# WL-POWER.net
KiCad netlist of a schematic drawn in Altium Designer
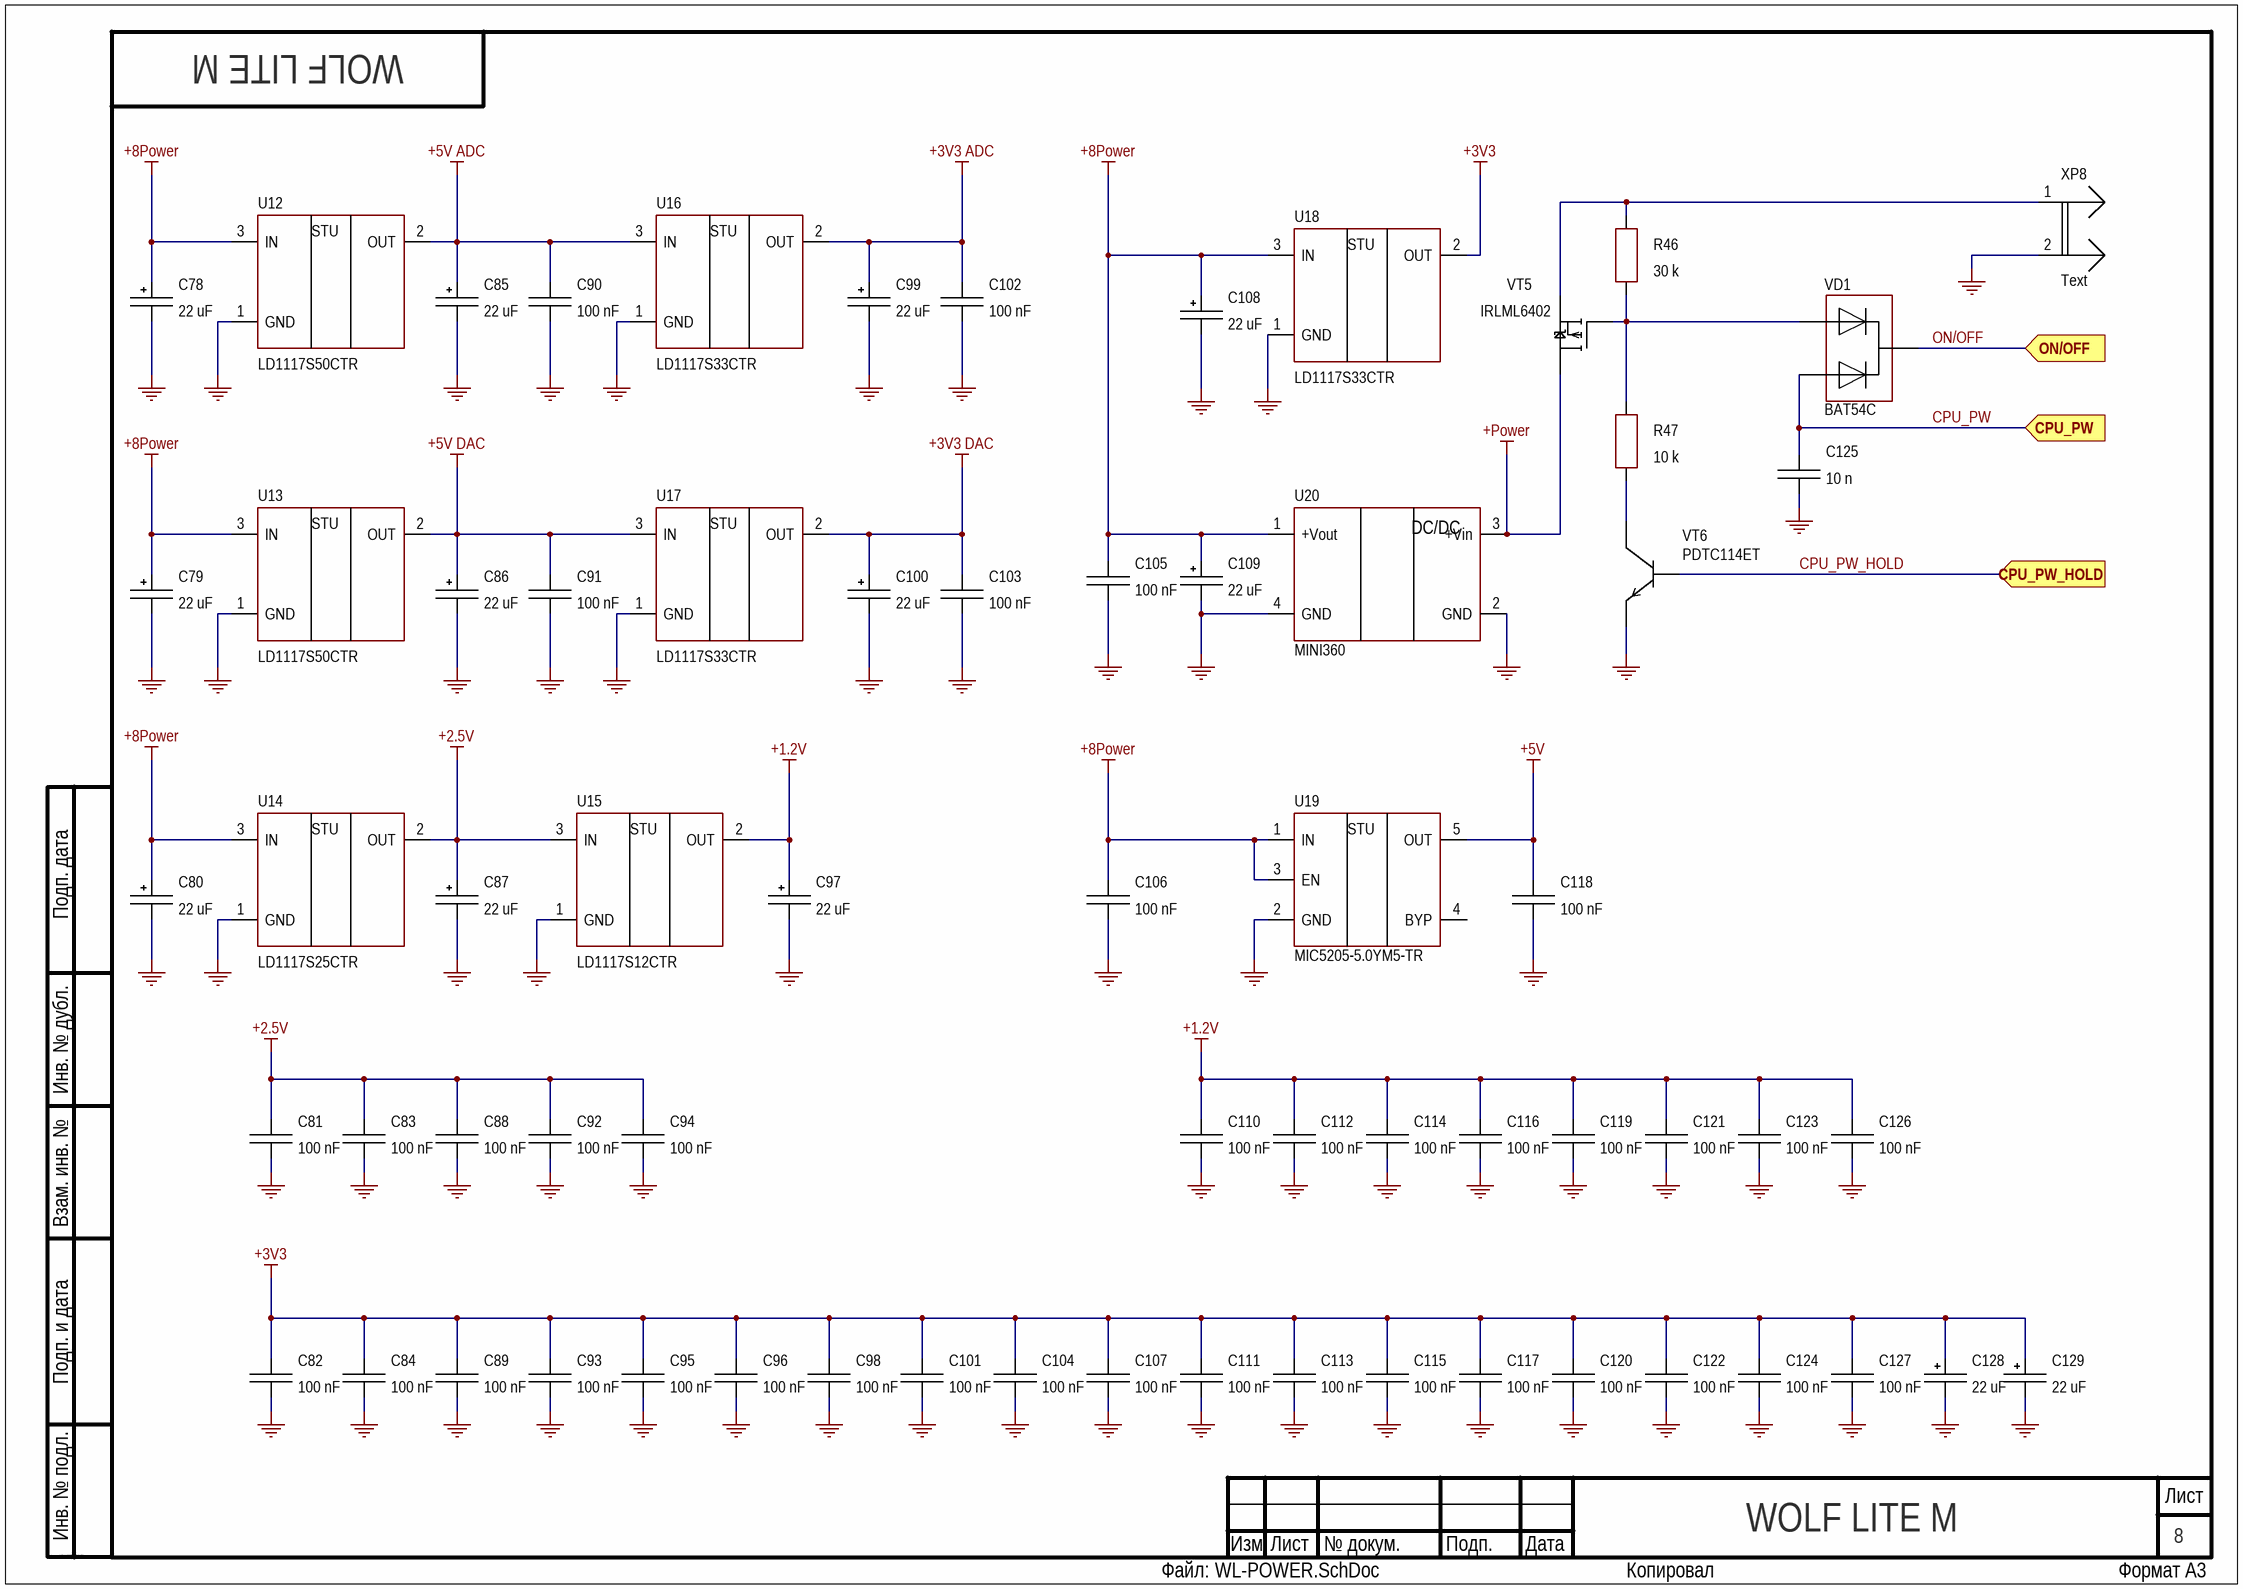
[diagram p0: WL-POWER.SchDoc]

(export (version "E")
  (design (tool "Eeschema 10.0.6"))
  (components
    (comp (ref "C78")
      (value "22 uF")
      (footprint "CAP-CASE B")
      (fields
        (field (name "MANUFACTURER") "Panasonic Electronic Components")
        (field (name "PART NUMBER") "EEE-1CA220WAR")
        (field (name "TOLERANCE") "±20%")
      )
      (libsource (lib "GOST") (part "Capacitor Polar"))
    )
    (comp (ref "C79")
      (value "22 uF")
      (footprint "CAP-CASE B")
      (fields
        (field (name "MANUFACTURER") "Panasonic Electronic Components")
        (field (name "PART NUMBER") "EEE-1CA220WAR")
        (field (name "TOLERANCE") "±20%")
      )
      (libsource (lib "GOST") (part "Capacitor Polar"))
    )
    (comp (ref "C80")
      (value "22 uF")
      (footprint "CAP-CASE B")
      (fields
        (field (name "MANUFACTURER") "Panasonic Electronic Components")
        (field (name "PART NUMBER") "EEE-1CA220WAR")
        (field (name "TOLERANCE") "±20%")
      )
      (libsource (lib "GOST") (part "Capacitor Polar"))
    )
    (comp (ref "C81")
      (value "100 nF")
      (footprint "C-0805-0.95")
      (fields
        (field (name "MANUFACTURER") "Yageo")
        (field (name "PART NUMBER") "CC0805KRX7R9BB104")
        (field (name "TOLERANCE") "±10%")
      )
      (libsource (lib "GOST") (part "Capacitor"))
    )
    (comp (ref "C82")
      (value "100 nF")
      (footprint "C-0805-0.95")
      (fields
        (field (name "MANUFACTURER") "Yageo")
        (field (name "PART NUMBER") "CC0805KRX7R9BB104")
        (field (name "TOLERANCE") "±10%")
      )
      (libsource (lib "GOST") (part "Capacitor"))
    )
    (comp (ref "C83")
      (value "100 nF")
      (footprint "C-0805-0.95")
      (fields
        (field (name "MANUFACTURER") "Yageo")
        (field (name "PART NUMBER") "CC0805KRX7R9BB104")
        (field (name "TOLERANCE") "±10%")
      )
      (libsource (lib "GOST") (part "Capacitor"))
    )
    (comp (ref "C84")
      (value "100 nF")
      (footprint "C-0805-0.95")
      (fields
        (field (name "MANUFACTURER") "Yageo")
        (field (name "PART NUMBER") "CC0805KRX7R9BB104")
        (field (name "TOLERANCE") "±10%")
      )
      (libsource (lib "GOST") (part "Capacitor"))
    )
    (comp (ref "C85")
      (value "22 uF")
      (footprint "CAP-CASE B")
      (fields
        (field (name "MANUFACTURER") "Panasonic Electronic Components")
        (field (name "PART NUMBER") "EEE-1CA220WAR")
        (field (name "TOLERANCE") "±20%")
      )
      (libsource (lib "GOST") (part "Capacitor Polar"))
    )
    (comp (ref "C86")
      (value "22 uF")
      (footprint "CAP-CASE B")
      (fields
        (field (name "MANUFACTURER") "Panasonic Electronic Components")
        (field (name "PART NUMBER") "EEE-1CA220WAR")
        (field (name "TOLERANCE") "±20%")
      )
      (libsource (lib "GOST") (part "Capacitor Polar"))
    )
    (comp (ref "C87")
      (value "22 uF")
      (footprint "CAP-CASE B")
      (fields
        (field (name "MANUFACTURER") "Panasonic Electronic Components")
        (field (name "PART NUMBER") "EEE-1CA220WAR")
        (field (name "TOLERANCE") "±20%")
      )
      (libsource (lib "GOST") (part "Capacitor Polar"))
    )
    (comp (ref "C88")
      (value "100 nF")
      (footprint "C-0805-0.95")
      (fields
        (field (name "MANUFACTURER") "Yageo")
        (field (name "PART NUMBER") "CC0805KRX7R9BB104")
        (field (name "TOLERANCE") "±10%")
      )
      (libsource (lib "GOST") (part "Capacitor"))
    )
    (comp (ref "C89")
      (value "100 nF")
      (footprint "C-0805-0.95")
      (fields
        (field (name "MANUFACTURER") "Yageo")
        (field (name "PART NUMBER") "CC0805KRX7R9BB104")
        (field (name "TOLERANCE") "±10%")
      )
      (libsource (lib "GOST") (part "Capacitor"))
    )
    (comp (ref "C90")
      (value "100 nF")
      (footprint "C-0805-0.95")
      (fields
        (field (name "MANUFACTURER") "Yageo")
        (field (name "PART NUMBER") "CC0805KRX7R9BB104")
        (field (name "TOLERANCE") "±10%")
      )
      (libsource (lib "GOST") (part "Capacitor"))
    )
    (comp (ref "C91")
      (value "100 nF")
      (footprint "C-0805-0.95")
      (fields
        (field (name "MANUFACTURER") "Yageo")
        (field (name "PART NUMBER") "CC0805KRX7R9BB104")
        (field (name "TOLERANCE") "±10%")
      )
      (libsource (lib "GOST") (part "Capacitor"))
    )
    (comp (ref "C92")
      (value "100 nF")
      (footprint "C-0805-0.95")
      (fields
        (field (name "MANUFACTURER") "Yageo")
        (field (name "PART NUMBER") "CC0805KRX7R9BB104")
        (field (name "TOLERANCE") "±10%")
      )
      (libsource (lib "GOST") (part "Capacitor"))
    )
    (comp (ref "C93")
      (value "100 nF")
      (footprint "C-0805-0.95")
      (fields
        (field (name "MANUFACTURER") "Yageo")
        (field (name "PART NUMBER") "CC0805KRX7R9BB104")
        (field (name "TOLERANCE") "±10%")
      )
      (libsource (lib "GOST") (part "Capacitor"))
    )
    (comp (ref "C94")
      (value "100 nF")
      (footprint "C-0805-0.95")
      (fields
        (field (name "MANUFACTURER") "Yageo")
        (field (name "PART NUMBER") "CC0805KRX7R9BB104")
        (field (name "TOLERANCE") "±10%")
      )
      (libsource (lib "GOST") (part "Capacitor"))
    )
    (comp (ref "C95")
      (value "100 nF")
      (footprint "C-0805-0.95")
      (fields
        (field (name "MANUFACTURER") "Yageo")
        (field (name "PART NUMBER") "CC0805KRX7R9BB104")
        (field (name "TOLERANCE") "±10%")
      )
      (libsource (lib "GOST") (part "Capacitor"))
    )
    (comp (ref "C96")
      (value "100 nF")
      (footprint "C-0805-0.95")
      (fields
        (field (name "MANUFACTURER") "Yageo")
        (field (name "PART NUMBER") "CC0805KRX7R9BB104")
        (field (name "TOLERANCE") "±10%")
      )
      (libsource (lib "GOST") (part "Capacitor"))
    )
    (comp (ref "C97")
      (value "22 uF")
      (footprint "CAP-CASE B")
      (fields
        (field (name "MANUFACTURER") "Panasonic Electronic Components")
        (field (name "PART NUMBER") "EEE-1CA220WAR")
        (field (name "TOLERANCE") "±20%")
      )
      (libsource (lib "GOST") (part "Capacitor Polar"))
    )
    (comp (ref "C98")
      (value "100 nF")
      (footprint "C-0805-0.95")
      (fields
        (field (name "MANUFACTURER") "Yageo")
        (field (name "PART NUMBER") "CC0805KRX7R9BB104")
        (field (name "TOLERANCE") "±10%")
      )
      (libsource (lib "GOST") (part "Capacitor"))
    )
    (comp (ref "C99")
      (value "22 uF")
      (footprint "CAP-CASE B")
      (fields
        (field (name "MANUFACTURER") "Panasonic Electronic Components")
        (field (name "PART NUMBER") "EEE-1CA220WAR")
        (field (name "TOLERANCE") "±20%")
      )
      (libsource (lib "GOST") (part "Capacitor Polar"))
    )
    (comp (ref "C100")
      (value "22 uF")
      (footprint "CAP-CASE B")
      (fields
        (field (name "MANUFACTURER") "Panasonic Electronic Components")
        (field (name "PART NUMBER") "EEE-1CA220WAR")
        (field (name "TOLERANCE") "±20%")
      )
      (libsource (lib "GOST") (part "Capacitor Polar"))
    )
    (comp (ref "C101")
      (value "100 nF")
      (footprint "C-0805-0.95")
      (fields
        (field (name "MANUFACTURER") "Yageo")
        (field (name "PART NUMBER") "CC0805KRX7R9BB104")
        (field (name "TOLERANCE") "±10%")
      )
      (libsource (lib "GOST") (part "Capacitor"))
    )
    (comp (ref "C102")
      (value "100 nF")
      (footprint "C-0805-0.95")
      (fields
        (field (name "MANUFACTURER") "Yageo")
        (field (name "PART NUMBER") "CC0805KRX7R9BB104")
        (field (name "TOLERANCE") "±10%")
      )
      (libsource (lib "GOST") (part "Capacitor"))
    )
    (comp (ref "C103")
      (value "100 nF")
      (footprint "C-0805-0.95")
      (fields
        (field (name "MANUFACTURER") "Yageo")
        (field (name "PART NUMBER") "CC0805KRX7R9BB104")
        (field (name "TOLERANCE") "±10%")
      )
      (libsource (lib "GOST") (part "Capacitor"))
    )
    (comp (ref "C104")
      (value "100 nF")
      (footprint "C-0805-0.95")
      (fields
        (field (name "MANUFACTURER") "Yageo")
        (field (name "PART NUMBER") "CC0805KRX7R9BB104")
        (field (name "TOLERANCE") "±10%")
      )
      (libsource (lib "GOST") (part "Capacitor"))
    )
    (comp (ref "C105")
      (value "100 nF")
      (footprint "C-0805-0.95")
      (fields
        (field (name "MANUFACTURER") "Yageo")
        (field (name "PART NUMBER") "CC0805KRX7R9BB104")
        (field (name "TOLERANCE") "±10%")
      )
      (libsource (lib "GOST") (part "Capacitor"))
    )
    (comp (ref "C106")
      (value "100 nF")
      (footprint "C-0805-0.95")
      (fields
        (field (name "MANUFACTURER") "Yageo")
        (field (name "PART NUMBER") "CC0805KRX7R9BB104")
        (field (name "TOLERANCE") "±10%")
      )
      (libsource (lib "GOST") (part "Capacitor"))
    )
    (comp (ref "C107")
      (value "100 nF")
      (footprint "C-0805-0.95")
      (fields
        (field (name "MANUFACTURER") "Yageo")
        (field (name "PART NUMBER") "CC0805KRX7R9BB104")
        (field (name "TOLERANCE") "±10%")
      )
      (libsource (lib "GOST") (part "Capacitor"))
    )
    (comp (ref "C108")
      (value "22 uF")
      (footprint "CAP-CASE B")
      (fields
        (field (name "MANUFACTURER") "Panasonic Electronic Components")
        (field (name "PART NUMBER") "EEE-1CA220WAR")
        (field (name "TOLERANCE") "±20%")
      )
      (libsource (lib "GOST") (part "Capacitor Polar"))
    )
    (comp (ref "C109")
      (value "22 uF")
      (footprint "CAP-CASE B")
      (fields
        (field (name "MANUFACTURER") "Panasonic Electronic Components")
        (field (name "PART NUMBER") "EEE-1CA220WAR")
        (field (name "TOLERANCE") "±20%")
      )
      (libsource (lib "GOST") (part "Capacitor Polar"))
    )
    (comp (ref "C110")
      (value "100 nF")
      (footprint "C-0805-0.95")
      (fields
        (field (name "MANUFACTURER") "Yageo")
        (field (name "PART NUMBER") "CC0805KRX7R9BB104")
        (field (name "TOLERANCE") "±10%")
      )
      (libsource (lib "GOST") (part "Capacitor"))
    )
    (comp (ref "C111")
      (value "100 nF")
      (footprint "C-0805-0.95")
      (fields
        (field (name "MANUFACTURER") "Yageo")
        (field (name "PART NUMBER") "CC0805KRX7R9BB104")
        (field (name "TOLERANCE") "±10%")
      )
      (libsource (lib "GOST") (part "Capacitor"))
    )
    (comp (ref "C112")
      (value "100 nF")
      (footprint "C-0805-0.95")
      (fields
        (field (name "MANUFACTURER") "Yageo")
        (field (name "PART NUMBER") "CC0805KRX7R9BB104")
        (field (name "TOLERANCE") "±10%")
      )
      (libsource (lib "GOST") (part "Capacitor"))
    )
    (comp (ref "C113")
      (value "100 nF")
      (footprint "C-0805-0.95")
      (fields
        (field (name "MANUFACTURER") "Yageo")
        (field (name "PART NUMBER") "CC0805KRX7R9BB104")
        (field (name "TOLERANCE") "±10%")
      )
      (libsource (lib "GOST") (part "Capacitor"))
    )
    (comp (ref "C114")
      (value "100 nF")
      (footprint "C-0805-0.95")
      (fields
        (field (name "MANUFACTURER") "Yageo")
        (field (name "PART NUMBER") "CC0805KRX7R9BB104")
        (field (name "TOLERANCE") "±10%")
      )
      (libsource (lib "GOST") (part "Capacitor"))
    )
    (comp (ref "C115")
      (value "100 nF")
      (footprint "C-0805-0.95")
      (fields
        (field (name "MANUFACTURER") "Yageo")
        (field (name "PART NUMBER") "CC0805KRX7R9BB104")
        (field (name "TOLERANCE") "±10%")
      )
      (libsource (lib "GOST") (part "Capacitor"))
    )
    (comp (ref "C116")
      (value "100 nF")
      (footprint "C-0805-0.95")
      (fields
        (field (name "MANUFACTURER") "Yageo")
        (field (name "PART NUMBER") "CC0805KRX7R9BB104")
        (field (name "TOLERANCE") "±10%")
      )
      (libsource (lib "GOST") (part "Capacitor"))
    )
    (comp (ref "C117")
      (value "100 nF")
      (footprint "C-0805-0.95")
      (fields
        (field (name "MANUFACTURER") "Yageo")
        (field (name "PART NUMBER") "CC0805KRX7R9BB104")
        (field (name "TOLERANCE") "±10%")
      )
      (libsource (lib "GOST") (part "Capacitor"))
    )
    (comp (ref "C118")
      (value "100 nF")
      (footprint "C-0805-0.95")
      (fields
        (field (name "MANUFACTURER") "Yageo")
        (field (name "PART NUMBER") "CC0805KRX7R9BB104")
        (field (name "TOLERANCE") "±10%")
      )
      (libsource (lib "GOST") (part "Capacitor"))
    )
    (comp (ref "C119")
      (value "100 nF")
      (footprint "C-0805-0.95")
      (fields
        (field (name "MANUFACTURER") "Yageo")
        (field (name "PART NUMBER") "CC0805KRX7R9BB104")
        (field (name "TOLERANCE") "±10%")
      )
      (libsource (lib "GOST") (part "Capacitor"))
    )
    (comp (ref "C120")
      (value "100 nF")
      (footprint "C-0805-0.95")
      (fields
        (field (name "MANUFACTURER") "Yageo")
        (field (name "PART NUMBER") "CC0805KRX7R9BB104")
        (field (name "TOLERANCE") "±10%")
      )
      (libsource (lib "GOST") (part "Capacitor"))
    )
    (comp (ref "C121")
      (value "100 nF")
      (footprint "C-0805-0.95")
      (fields
        (field (name "MANUFACTURER") "Yageo")
        (field (name "PART NUMBER") "CC0805KRX7R9BB104")
        (field (name "TOLERANCE") "±10%")
      )
      (libsource (lib "GOST") (part "Capacitor"))
    )
    (comp (ref "C122")
      (value "100 nF")
      (footprint "C-0805-0.95")
      (fields
        (field (name "MANUFACTURER") "Yageo")
        (field (name "PART NUMBER") "CC0805KRX7R9BB104")
        (field (name "TOLERANCE") "±10%")
      )
      (libsource (lib "GOST") (part "Capacitor"))
    )
    (comp (ref "C123")
      (value "100 nF")
      (footprint "C-0805-0.95")
      (fields
        (field (name "MANUFACTURER") "Yageo")
        (field (name "PART NUMBER") "CC0805KRX7R9BB104")
        (field (name "TOLERANCE") "±10%")
      )
      (libsource (lib "GOST") (part "Capacitor"))
    )
    (comp (ref "C124")
      (value "100 nF")
      (footprint "C-0805-0.95")
      (fields
        (field (name "MANUFACTURER") "Yageo")
        (field (name "PART NUMBER") "CC0805KRX7R9BB104")
        (field (name "TOLERANCE") "±10%")
      )
      (libsource (lib "GOST") (part "Capacitor"))
    )
    (comp (ref "C125")
      (value "10 n")
      (footprint "C-0805-0.7")
      (fields
        (field (name "MANUFACTURER") "Yageo")
        (field (name "PART NUMBER") "CC0805KRX7R9BB103")
        (field (name "TOLERANCE") "±10%")
      )
      (libsource (lib "GOST") (part "Capacitor"))
    )
    (comp (ref "C126")
      (value "100 nF")
      (footprint "C-0805-0.95")
      (fields
        (field (name "MANUFACTURER") "Yageo")
        (field (name "PART NUMBER") "CC0805KRX7R9BB104")
        (field (name "TOLERANCE") "±10%")
      )
      (libsource (lib "GOST") (part "Capacitor"))
    )
    (comp (ref "C127")
      (value "100 nF")
      (footprint "C-0805-0.95")
      (fields
        (field (name "MANUFACTURER") "Yageo")
        (field (name "PART NUMBER") "CC0805KRX7R9BB104")
        (field (name "TOLERANCE") "±10%")
      )
      (libsource (lib "GOST") (part "Capacitor"))
    )
    (comp (ref "C128")
      (value "22 uF")
      (footprint "CAP-CASE B")
      (fields
        (field (name "MANUFACTURER") "Panasonic Electronic Components")
        (field (name "PART NUMBER") "EEE-1CA220WAR")
        (field (name "TOLERANCE") "±20%")
      )
      (libsource (lib "GOST") (part "Capacitor Polar"))
    )
    (comp (ref "C129")
      (value "22 uF")
      (footprint "CAP-CASE B")
      (fields
        (field (name "MANUFACTURER") "Panasonic Electronic Components")
        (field (name "PART NUMBER") "EEE-1CA220WAR")
        (field (name "TOLERANCE") "±20%")
      )
      (libsource (lib "GOST") (part "Capacitor Polar"))
    )
    (comp (ref "R46")
      (value "30 k")
      (footprint "R-0805")
      (fields
        (field (name "MANUFACTURER") "Yageo")
        (field (name "PART NUMBER") "RC0805JR-0730KL")
        (field (name "POWER") "0,125 W")
      )
      (libsource (lib "GOST") (part "Resistor"))
    )
    (comp (ref "R47")
      (value "10 k")
      (footprint "R-0805")
      (fields
        (field (name "MANUFACTURER") "Yageo")
        (field (name "PART NUMBER") "RC0805JR-0710KL")
        (field (name "POWER") "0,125 W")
      )
      (libsource (lib "") (part "Resistor_1"))
    )
    (comp (ref "U12")
      (value "LD1117S50CTR")
      (footprint "SOT-223")
      (description "IC REG LINEAR")
      (fields (field (name "MANUFACTURER") "STMicroelectronics"))
      (libsource (lib "GOST") (part "LD1117"))
    )
    (comp (ref "U13")
      (value "LD1117S50CTR")
      (footprint "SOT-223")
      (description "IC REG LINEAR")
      (fields (field (name "MANUFACTURER") "STMicroelectronics"))
      (libsource (lib "GOST") (part "LD1117"))
    )
    (comp (ref "U14")
      (value "LD1117S25CTR")
      (footprint "SOT-223")
      (description "IC REG LINEAR")
      (fields (field (name "MANUFACTURER") "STMicroelectronics"))
      (libsource (lib "GOST") (part "LD1117"))
    )
    (comp (ref "U15")
      (value "LD1117S12CTR")
      (footprint "SOT-223")
      (description "IC REG LINEAR")
      (fields (field (name "MANUFACTURER") "STMicroelectronics"))
      (libsource (lib "GOST") (part "LD1117"))
    )
    (comp (ref "U16")
      (value "LD1117S33CTR")
      (footprint "SOT-223")
      (description "IC REG LINEAR")
      (fields (field (name "MANUFACTURER") "STMicroelectronics"))
      (libsource (lib "GOST") (part "LD1117"))
    )
    (comp (ref "U17")
      (value "LD1117S33CTR")
      (footprint "SOT-223")
      (description "IC REG LINEAR")
      (fields (field (name "MANUFACTURER") "STMicroelectronics"))
      (libsource (lib "GOST") (part "LD1117"))
    )
    (comp (ref "U18")
      (value "LD1117S33CTR")
      (footprint "SOT-223")
      (description "IC REG LINEAR")
      (fields (field (name "MANUFACTURER") "STMicroelectronics"))
      (libsource (lib "GOST") (part "LD1117"))
    )
    (comp (ref "U19")
      (value "MIC5205-5.0YM5-TR")
      (footprint "SOT-23-5")
      (description "IC REG LINEAR  150MA SOT-23-5")
      (fields (field (name "MANUFACTURER") "Microchip Technology"))
      (libsource (lib "GOST") (part "MIC5205"))
    )
    (comp (ref "U20")
      (value "MINI360")
      (footprint "MINI360")
      (description "DC/DC")
      (libsource (lib "GOST") (part "MINI360"))
    )
    (comp (ref "VD1")
      (value "BAT54C")
      (footprint "SOT-23")
      (fields (field (name "PART NUMBER") "BAT54CLT3G") (field (name "MANUFACTURER") "ON Semiconductor"))
      (libsource (lib "GOST") (part "Schottky Array Common C"))
    )
    (comp (ref "VT5")
      (value "IRLML6402")
      (footprint "SOT-23")
      (fields
        (field (name "PART NUMBER") "IRLML6402TRPBF")
        (field (name "MANUFACTURER") "Infineon Technologies")
      )
      (libsource (lib "GOST") (part "MOSFET-P"))
    )
    (comp (ref "VT6")
      (value "PDTC114ET")
      (footprint "SOT-23")
      (fields (field (name "PART NUMBER") "PDTC114ET,215") (field (name "MANUFACTURER") "Nexperia USA Inc."))
      (libsource (lib "GOST") (part "BJT-NPN"))
    )
    (comp (ref "XP8")
      (value "Text")
      (footprint "61900211121")
      (fields (field (name "PART NUMBER") "61900211121") (field (name "MANUFACTURER") "Würth Elektronik"))
      (libsource (lib "GOST") (part "Con-2-M"))
    )
  )
  (nets
    (net (code "1") (name "+1.2V") (class "Default")
      (node (ref "C110") (pin "1") (pinfunction "1_1") (pintype "passive"))
      (node (ref "C112") (pin "1") (pinfunction "1_1") (pintype "passive"))
      (node (ref "C114") (pin "1") (pinfunction "1_1") (pintype "passive"))
      (node (ref "C116") (pin "1") (pinfunction "1_1") (pintype "passive"))
      (node (ref "C119") (pin "1") (pinfunction "1_1") (pintype "passive"))
      (node (ref "C121") (pin "1") (pinfunction "1_1") (pintype "passive"))
      (node (ref "C123") (pin "1") (pinfunction "1_1") (pintype "passive"))
      (node (ref "C126") (pin "1") (pinfunction "1_1") (pintype "passive"))
      (node (ref "C97") (pin "1") (pinfunction "1_1") (pintype "passive"))
      (node (ref "U15") (pin "2") (pinfunction "OUT_2") (pintype "passive"))
    )
    (net (code "2") (name "+2.5V") (class "Default")
      (node (ref "C81") (pin "1") (pinfunction "1_1") (pintype "passive"))
      (node (ref "C83") (pin "1") (pinfunction "1_1") (pintype "passive"))
      (node (ref "C87") (pin "1") (pinfunction "1_1") (pintype "passive"))
      (node (ref "C88") (pin "1") (pinfunction "1_1") (pintype "passive"))
      (node (ref "C92") (pin "1") (pinfunction "1_1") (pintype "passive"))
      (node (ref "C94") (pin "1") (pinfunction "1_1") (pintype "passive"))
      (node (ref "U14") (pin "2") (pinfunction "OUT_2") (pintype "passive"))
      (node (ref "U15") (pin "3") (pinfunction "IN_3") (pintype "passive"))
    )
    (net (code "3") (name "+3V3") (class "Default")
      (node (ref "C101") (pin "1") (pinfunction "1_1") (pintype "passive"))
      (node (ref "C104") (pin "1") (pinfunction "1_1") (pintype "passive"))
      (node (ref "C107") (pin "1") (pinfunction "1_1") (pintype "passive"))
      (node (ref "C111") (pin "1") (pinfunction "1_1") (pintype "passive"))
      (node (ref "C113") (pin "1") (pinfunction "1_1") (pintype "passive"))
      (node (ref "C115") (pin "1") (pinfunction "1_1") (pintype "passive"))
      (node (ref "C117") (pin "1") (pinfunction "1_1") (pintype "passive"))
      (node (ref "C120") (pin "1") (pinfunction "1_1") (pintype "passive"))
      (node (ref "C122") (pin "1") (pinfunction "1_1") (pintype "passive"))
      (node (ref "C124") (pin "1") (pinfunction "1_1") (pintype "passive"))
      (node (ref "C127") (pin "1") (pinfunction "1_1") (pintype "passive"))
      (node (ref "C128") (pin "1") (pinfunction "1_1") (pintype "passive"))
      (node (ref "C129") (pin "1") (pinfunction "1_1") (pintype "passive"))
      (node (ref "C82") (pin "1") (pinfunction "1_1") (pintype "passive"))
      (node (ref "C84") (pin "1") (pinfunction "1_1") (pintype "passive"))
      (node (ref "C89") (pin "1") (pinfunction "1_1") (pintype "passive"))
      (node (ref "C93") (pin "1") (pinfunction "1_1") (pintype "passive"))
      (node (ref "C95") (pin "1") (pinfunction "1_1") (pintype "passive"))
      (node (ref "C96") (pin "1") (pinfunction "1_1") (pintype "passive"))
      (node (ref "C98") (pin "1") (pinfunction "1_1") (pintype "passive"))
      (node (ref "U18") (pin "2") (pinfunction "OUT_2") (pintype "passive"))
    )
    (net (code "4") (name "+3V3 ADC") (class "Default")
      (node (ref "C102") (pin "2") (pinfunction "2_2") (pintype "passive"))
      (node (ref "C99") (pin "1") (pinfunction "1_1") (pintype "passive"))
      (node (ref "U16") (pin "2") (pinfunction "OUT_2") (pintype "passive"))
    )
    (net (code "5") (name "+3V3 DAC") (class "Default")
      (node (ref "C100") (pin "1") (pinfunction "1_1") (pintype "passive"))
      (node (ref "C103") (pin "2") (pinfunction "2_2") (pintype "passive"))
      (node (ref "U17") (pin "2") (pinfunction "OUT_2") (pintype "passive"))
    )
    (net (code "6") (name "+5V") (class "Default")
      (node (ref "C118") (pin "1") (pinfunction "1_1") (pintype "passive"))
      (node (ref "U19") (pin "5") (pinfunction "OUT_5") (pintype "passive"))
    )
    (net (code "7") (name "+5V ADC") (class "Default")
      (node (ref "C85") (pin "1") (pinfunction "1_1") (pintype "passive"))
      (node (ref "C90") (pin "2") (pinfunction "2_2") (pintype "passive"))
      (node (ref "U12") (pin "2") (pinfunction "OUT_2") (pintype "passive"))
      (node (ref "U16") (pin "3") (pinfunction "IN_3") (pintype "passive"))
    )
    (net (code "8") (name "+5V DAC") (class "Default")
      (node (ref "C86") (pin "1") (pinfunction "1_1") (pintype "passive"))
      (node (ref "C91") (pin "2") (pinfunction "2_2") (pintype "passive"))
      (node (ref "U13") (pin "2") (pinfunction "OUT_2") (pintype "passive"))
      (node (ref "U17") (pin "3") (pinfunction "IN_3") (pintype "passive"))
    )
    (net (code "9") (name "+8Power") (class "Default")
      (node (ref "C105") (pin "2") (pinfunction "2_2") (pintype "passive"))
      (node (ref "C106") (pin "1") (pinfunction "1_1") (pintype "passive"))
      (node (ref "C108") (pin "1") (pinfunction "1_1") (pintype "passive"))
      (node (ref "C109") (pin "1") (pinfunction "1_1") (pintype "passive"))
      (node (ref "C78") (pin "1") (pinfunction "1_1") (pintype "passive"))
      (node (ref "C79") (pin "1") (pinfunction "1_1") (pintype "passive"))
      (node (ref "C80") (pin "1") (pinfunction "1_1") (pintype "passive"))
      (node (ref "U12") (pin "3") (pinfunction "IN_3") (pintype "passive"))
      (node (ref "U13") (pin "3") (pinfunction "IN_3") (pintype "passive"))
      (node (ref "U14") (pin "3") (pinfunction "IN_3") (pintype "passive"))
      (node (ref "U18") (pin "3") (pinfunction "IN_3") (pintype "passive"))
      (node (ref "U19") (pin "1") (pinfunction "IN_1") (pintype "passive"))
      (node (ref "U19") (pin "3") (pinfunction "EN_3") (pintype "passive"))
      (node (ref "U20") (pin "1") (pinfunction "+Vout_1") (pintype "passive"))
    )
    (net (code "10") (name "+Power") (class "Default")
      (node (ref "U20") (pin "3") (pinfunction "+Vin_3") (pintype "passive"))
      (node (ref "VT5") (pin "3") (pinfunction "D_3") (pintype "passive"))
    )
    (net (code "11") (name "/CPU_PW") (class "Default")
      (node (ref "C125") (pin "1") (pinfunction "1_1") (pintype "passive"))
      (node (ref "VD1") (pin "2") (pinfunction "2_2") (pintype "passive"))
    )
    (net (code "12") (name "/CPU_PW_HOLD") (class "Default")
      (node (ref "VT6") (pin "1") (pinfunction "1_1") (pintype "passive"))
    )
    (net (code "13") (name "/ON{slash}OFF") (class "Default")
      (node (ref "VD1") (pin "3") (pinfunction "3_3") (pintype "passive"))
    )
    (net (code "14") (name "GND") (class "Default")
      (node (ref "C100") (pin "2") (pinfunction "2_2") (pintype "passive"))
      (node (ref "C101") (pin "2") (pinfunction "2_2") (pintype "passive"))
      (node (ref "C102") (pin "1") (pinfunction "1_1") (pintype "passive"))
      (node (ref "C103") (pin "1") (pinfunction "1_1") (pintype "passive"))
      (node (ref "C104") (pin "2") (pinfunction "2_2") (pintype "passive"))
      (node (ref "C105") (pin "1") (pinfunction "1_1") (pintype "passive"))
      (node (ref "C106") (pin "2") (pinfunction "2_2") (pintype "passive"))
      (node (ref "C107") (pin "2") (pinfunction "2_2") (pintype "passive"))
      (node (ref "C108") (pin "2") (pinfunction "2_2") (pintype "passive"))
      (node (ref "C109") (pin "2") (pinfunction "2_2") (pintype "passive"))
      (node (ref "C110") (pin "2") (pinfunction "2_2") (pintype "passive"))
      (node (ref "C111") (pin "2") (pinfunction "2_2") (pintype "passive"))
      (node (ref "C112") (pin "2") (pinfunction "2_2") (pintype "passive"))
      (node (ref "C113") (pin "2") (pinfunction "2_2") (pintype "passive"))
      (node (ref "C114") (pin "2") (pinfunction "2_2") (pintype "passive"))
      (node (ref "C115") (pin "2") (pinfunction "2_2") (pintype "passive"))
      (node (ref "C116") (pin "2") (pinfunction "2_2") (pintype "passive"))
      (node (ref "C117") (pin "2") (pinfunction "2_2") (pintype "passive"))
      (node (ref "C118") (pin "2") (pinfunction "2_2") (pintype "passive"))
      (node (ref "C119") (pin "2") (pinfunction "2_2") (pintype "passive"))
      (node (ref "C120") (pin "2") (pinfunction "2_2") (pintype "passive"))
      (node (ref "C121") (pin "2") (pinfunction "2_2") (pintype "passive"))
      (node (ref "C122") (pin "2") (pinfunction "2_2") (pintype "passive"))
      (node (ref "C123") (pin "2") (pinfunction "2_2") (pintype "passive"))
      (node (ref "C124") (pin "2") (pinfunction "2_2") (pintype "passive"))
      (node (ref "C125") (pin "2") (pinfunction "2_2") (pintype "passive"))
      (node (ref "C126") (pin "2") (pinfunction "2_2") (pintype "passive"))
      (node (ref "C127") (pin "2") (pinfunction "2_2") (pintype "passive"))
      (node (ref "C128") (pin "2") (pinfunction "2_2") (pintype "passive"))
      (node (ref "C129") (pin "2") (pinfunction "2_2") (pintype "passive"))
      (node (ref "C78") (pin "2") (pinfunction "2_2") (pintype "passive"))
      (node (ref "C79") (pin "2") (pinfunction "2_2") (pintype "passive"))
      (node (ref "C80") (pin "2") (pinfunction "2_2") (pintype "passive"))
      (node (ref "C81") (pin "2") (pinfunction "2_2") (pintype "passive"))
      (node (ref "C82") (pin "2") (pinfunction "2_2") (pintype "passive"))
      (node (ref "C83") (pin "2") (pinfunction "2_2") (pintype "passive"))
      (node (ref "C84") (pin "2") (pinfunction "2_2") (pintype "passive"))
      (node (ref "C85") (pin "2") (pinfunction "2_2") (pintype "passive"))
      (node (ref "C86") (pin "2") (pinfunction "2_2") (pintype "passive"))
      (node (ref "C87") (pin "2") (pinfunction "2_2") (pintype "passive"))
      (node (ref "C88") (pin "2") (pinfunction "2_2") (pintype "passive"))
      (node (ref "C89") (pin "2") (pinfunction "2_2") (pintype "passive"))
      (node (ref "C90") (pin "1") (pinfunction "1_1") (pintype "passive"))
      (node (ref "C91") (pin "1") (pinfunction "1_1") (pintype "passive"))
      (node (ref "C92") (pin "2") (pinfunction "2_2") (pintype "passive"))
      (node (ref "C93") (pin "2") (pinfunction "2_2") (pintype "passive"))
      (node (ref "C94") (pin "2") (pinfunction "2_2") (pintype "passive"))
      (node (ref "C95") (pin "2") (pinfunction "2_2") (pintype "passive"))
      (node (ref "C96") (pin "2") (pinfunction "2_2") (pintype "passive"))
      (node (ref "C97") (pin "2") (pinfunction "2_2") (pintype "passive"))
      (node (ref "C98") (pin "2") (pinfunction "2_2") (pintype "passive"))
      (node (ref "C99") (pin "2") (pinfunction "2_2") (pintype "passive"))
      (node (ref "U12") (pin "1") (pinfunction "GND_1") (pintype "passive"))
      (node (ref "U13") (pin "1") (pinfunction "GND_1") (pintype "passive"))
      (node (ref "U14") (pin "1") (pinfunction "GND_1") (pintype "passive"))
      (node (ref "U15") (pin "1") (pinfunction "GND_1") (pintype "passive"))
      (node (ref "U16") (pin "1") (pinfunction "GND_1") (pintype "passive"))
      (node (ref "U17") (pin "1") (pinfunction "GND_1") (pintype "passive"))
      (node (ref "U18") (pin "1") (pinfunction "GND_1") (pintype "passive"))
      (node (ref "U19") (pin "2") (pinfunction "GND_2") (pintype "passive"))
      (node (ref "U20") (pin "2") (pinfunction "GND_2") (pintype "passive"))
      (node (ref "U20") (pin "4") (pinfunction "GND_4") (pintype "passive"))
      (node (ref "VT6") (pin "2") (pinfunction "2_2") (pintype "passive"))
      (node (ref "XP8") (pin "2") (pintype "passive"))
    )
    (net (code "15") (name "Net-(R47-Pad2)") (class "Default")
      (node (ref "R47") (pin "2") (pinfunction "2_2") (pintype "passive"))
      (node (ref "VT6") (pin "3") (pinfunction "3_3") (pintype "passive"))
    )
    (net (code "16") (name "Net-(VT5-G)") (class "Default")
      (node (ref "R46") (pin "1") (pinfunction "1_1") (pintype "passive"))
      (node (ref "R47") (pin "1") (pinfunction "1_1") (pintype "passive"))
      (node (ref "VD1") (pin "1") (pinfunction "1_1") (pintype "passive"))
      (node (ref "VT5") (pin "1") (pinfunction "G_1") (pintype "passive"))
    )
    (net (code "17") (name "Net-(VT5-S)") (class "Default")
      (node (ref "R46") (pin "2") (pinfunction "2_2") (pintype "passive"))
      (node (ref "VT5") (pin "2") (pinfunction "S_2") (pintype "passive"))
      (node (ref "XP8") (pin "1") (pintype "passive"))
    )
    (net (code "18") (name "unconnected-(U19-BYP-Pad4)") (class "Default")
      (node (ref "U19") (pin "4") (pinfunction "BYP_4") (pintype "passive"))
    )
  )
)
